# TOP_pcb_redonda_intento_taladros.net
KiCad netlist of a schematic drawn in EAGLE
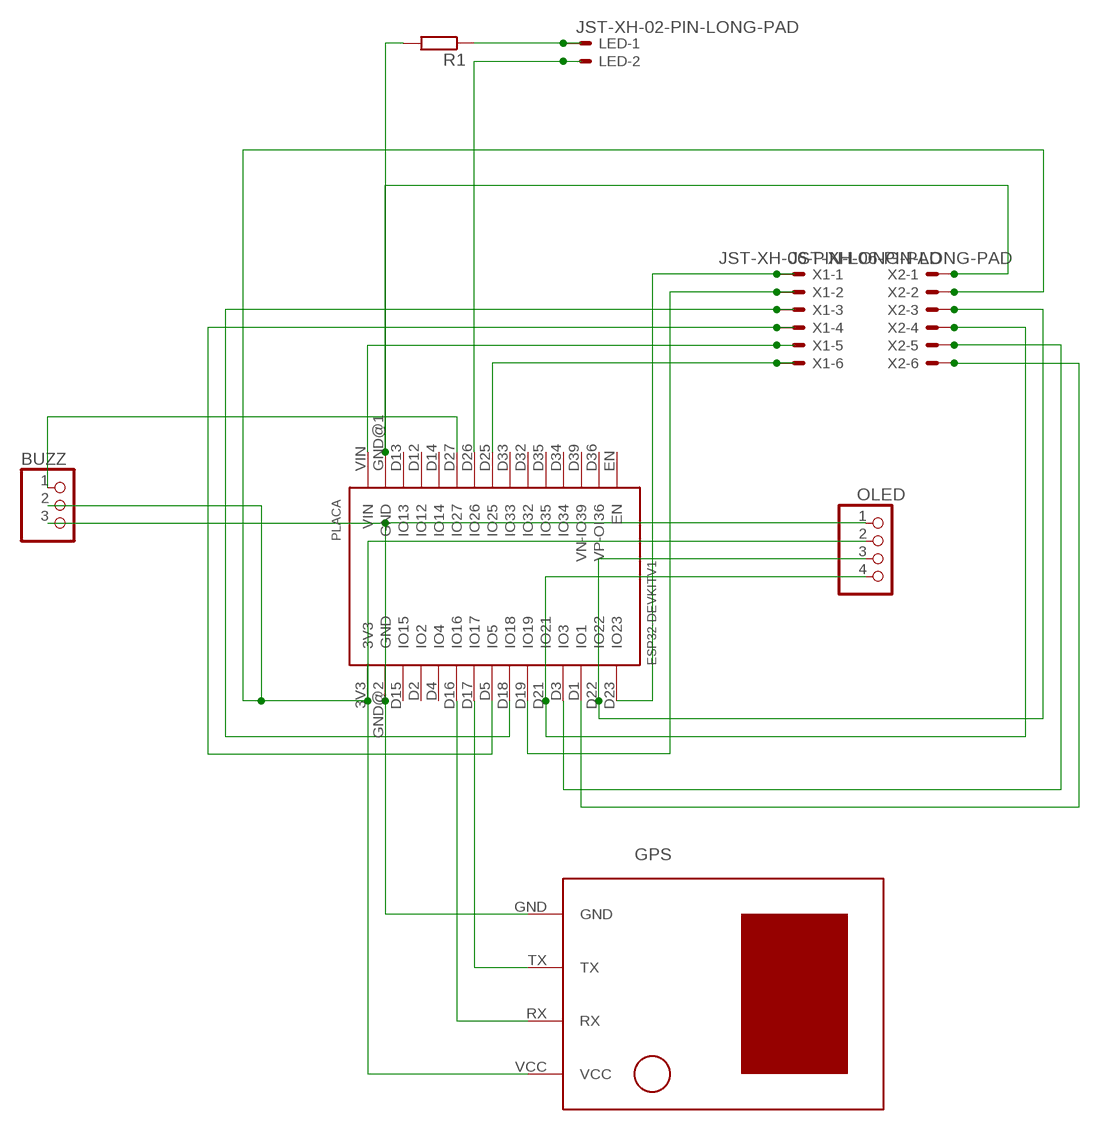
[diagram p0: schematic, sheet 1]

(export (version "E")
  (design (tool "Eeschema 10.0.6"))
  (components
    (comp (ref "BUZZ")
      (value "PINHD-1X3")
      (footprint "eagle-import:1X03")
      (libsource (lib "eagle-import") (part "PINHD-1X3"))
    )
    (comp (ref "GPS")
      (value "U-BLOX-NEO6V2")
      (footprint "eagle-import:U-BLOX-NEO6V2")
      (libsource (lib "eagle-import") (part "U-BLOX-NEO6V2"))
    )
    (comp (ref "LED")
      (value "JST-XH-02-PIN-LONG-PAD")
      (footprint "eagle-import:JST-XH-02-PACKAGE-LONG-PAD")
      (libsource (lib "eagle-import") (part "JST-XH-02-PIN-LONG-PAD"))
    )
    (comp (ref "OLED")
      (value "PINHD-1X4")
      (footprint "eagle-import:1X04")
      (libsource (lib "eagle-import") (part "PINHD-1X4"))
    )
    (comp (ref "PLACA")
      (value "ESP32DEVKITV1")
      (footprint "eagle-import:ESP32-DEVKITV1")
      (libsource (lib "eagle-import") (part "ESP32DEVKITV1"))
    )
    (comp (ref "R1")
      (value "R-EU_0207/10")
      (footprint "eagle-import:0207_10")
      (libsource (lib "eagle-import") (part "R-EU_0207/10"))
    )
    (comp (ref "X1")
      (value "JST-XH-06-PIN-LONG-PAD")
      (footprint "eagle-import:JST-XH-06-PACKAGE-LONG-PAD")
      (libsource (lib "eagle-import") (part "JST-XH-06-PIN-LONG-PAD"))
    )
    (comp (ref "X2")
      (value "JST-XH-06-PIN-LONG-PAD")
      (footprint "eagle-import:JST-XH-06-PACKAGE-LONG-PAD")
      (libsource (lib "eagle-import") (part "JST-XH-06-PIN-LONG-PAD"))
    )
  )
  (nets
    (net (code "1") (name "/GPS") (class "Default")
      (node (ref "BUZZ") (pin "3") (pinfunction "3_3") (pintype "passive"))
      (node (ref "GPS") (pin "GND") (pinfunction "GND_GND") (pintype "bidirectional"))
      (node (ref "OLED") (pin "1") (pinfunction "1_1") (pintype "passive"))
      (node (ref "PLACA") (pin "GND@2") (pinfunction "GND_GND@2") (pintype "bidirectional"))
    )
    (net (code "2") (name "Net-(LEDA-S)") (class "Default")
      (node (ref "LED") (pin "1") (pinfunction "S_1") (pintype "passive"))
      (node (ref "R1") (pin "1") (pinfunction "1_1") (pintype "passive"))
    )
    (net (code "3") (name "Net-(LEDB-S)") (class "Default")
      (node (ref "LED") (pin "2") (pinfunction "S_2") (pintype "passive"))
      (node (ref "PLACA") (pin "D26") (pinfunction "IO26_D26") (pintype "bidirectional"))
    )
    (net (code "4") (name "Net-(PLACA-IO1)") (class "Default")
      (node (ref "PLACA") (pin "D1") (pinfunction "IO1_D1") (pintype "bidirectional"))
      (node (ref "X2") (pin "6") (pinfunction "S_6") (pintype "passive"))
    )
    (net (code "5") (name "Net-(PLACA-IO3)") (class "Default")
      (node (ref "PLACA") (pin "D3") (pinfunction "IO3_D3") (pintype "bidirectional"))
      (node (ref "X2") (pin "5") (pinfunction "S_5") (pintype "passive"))
    )
    (net (code "6") (name "Net-(PLACA-IO5)") (class "Default")
      (node (ref "PLACA") (pin "D5") (pinfunction "IO5_D5") (pintype "bidirectional"))
      (node (ref "X1") (pin "4") (pinfunction "S_4") (pintype "passive"))
    )
    (net (code "7") (name "Net-(PLACA-IO16)") (class "Default")
      (node (ref "GPS") (pin "RX") (pinfunction "RX_RX") (pintype "bidirectional"))
      (node (ref "PLACA") (pin "D16") (pinfunction "IO16_D16") (pintype "bidirectional"))
    )
    (net (code "8") (name "Net-(PLACA-IO17)") (class "Default")
      (node (ref "GPS") (pin "TX") (pinfunction "TX_TX") (pintype "bidirectional"))
      (node (ref "PLACA") (pin "D17") (pinfunction "IO17_D17") (pintype "bidirectional"))
    )
    (net (code "9") (name "Net-(PLACA-IO18)") (class "Default")
      (node (ref "PLACA") (pin "D18") (pinfunction "IO18_D18") (pintype "bidirectional"))
      (node (ref "X1") (pin "3") (pinfunction "S_3") (pintype "passive"))
    )
    (net (code "10") (name "Net-(PLACA-IO19)") (class "Default")
      (node (ref "PLACA") (pin "D19") (pinfunction "IO19_D19") (pintype "bidirectional"))
      (node (ref "X1") (pin "2") (pinfunction "S_2") (pintype "passive"))
    )
    (net (code "11") (name "Net-(PLACA-IO21)") (class "Default")
      (node (ref "OLED") (pin "4") (pinfunction "4_4") (pintype "passive"))
      (node (ref "PLACA") (pin "D21") (pinfunction "IO21_D21") (pintype "bidirectional"))
      (node (ref "X2") (pin "4") (pinfunction "S_4") (pintype "passive"))
    )
    (net (code "12") (name "Net-(PLACA-IO22)") (class "Default")
      (node (ref "OLED") (pin "3") (pinfunction "3_3") (pintype "passive"))
      (node (ref "PLACA") (pin "D22") (pinfunction "IO22_D22") (pintype "bidirectional"))
      (node (ref "X2") (pin "3") (pinfunction "S_3") (pintype "passive"))
    )
    (net (code "13") (name "Net-(PLACA-IO23)") (class "Default")
      (node (ref "PLACA") (pin "D23") (pinfunction "IO23_D23") (pintype "bidirectional"))
      (node (ref "X1") (pin "1") (pinfunction "S_1") (pintype "passive"))
    )
    (net (code "14") (name "Net-(PLACA-IO25)") (class "Default")
      (node (ref "PLACA") (pin "D25") (pinfunction "IO25_D25") (pintype "bidirectional"))
      (node (ref "X1") (pin "6") (pinfunction "S_6") (pintype "passive"))
    )
    (net (code "15") (name "Net-(PLACA-IO27)") (class "Default")
      (node (ref "BUZZ") (pin "1") (pinfunction "1_1") (pintype "passive"))
      (node (ref "PLACA") (pin "D27") (pinfunction "IO27_D27") (pintype "bidirectional"))
    )
    (net (code "16") (name "Net-(X1E-S)") (class "Default")
      (node (ref "PLACA") (pin "VIN") (pinfunction "VIN_VIN") (pintype "bidirectional"))
      (node (ref "X1") (pin "5") (pinfunction "S_5") (pintype "passive"))
    )
    (net (code "17") (name "Net-(X2A-S)") (class "Default")
      (node (ref "PLACA") (pin "GND@1") (pinfunction "GND_GND@1") (pintype "bidirectional"))
      (node (ref "R1") (pin "2") (pinfunction "2_2") (pintype "passive"))
      (node (ref "X2") (pin "1") (pinfunction "S_1") (pintype "passive"))
    )
    (net (code "18") (name "Net-(X2B-S)") (class "Default")
      (node (ref "BUZZ") (pin "2") (pinfunction "2_2") (pintype "passive"))
      (node (ref "GPS") (pin "VCC") (pinfunction "VCC_VCC") (pintype "bidirectional"))
      (node (ref "OLED") (pin "2") (pinfunction "2_2") (pintype "passive"))
      (node (ref "PLACA") (pin "3V3") (pinfunction "3V3_3V3") (pintype "bidirectional"))
      (node (ref "X2") (pin "2") (pinfunction "S_2") (pintype "passive"))
    )
    (net (code "19") (name "unconnected-(PLACA-IO2-PadD2)") (class "Default")
      (node (ref "PLACA") (pin "D2") (pinfunction "IO2_D2") (pintype "bidirectional"))
    )
    (net (code "20") (name "unconnected-(PLACA-IO4-PadD4)") (class "Default")
      (node (ref "PLACA") (pin "D4") (pinfunction "IO4_D4") (pintype "bidirectional"))
    )
    (net (code "21") (name "unconnected-(PLACA-IO12-PadD12)") (class "Default")
      (node (ref "PLACA") (pin "D12") (pinfunction "IO12_D12") (pintype "bidirectional"))
    )
    (net (code "22") (name "unconnected-(PLACA-IO13-PadD13)") (class "Default")
      (node (ref "PLACA") (pin "D13") (pinfunction "IO13_D13") (pintype "bidirectional"))
    )
    (net (code "23") (name "unconnected-(PLACA-IO14-PadD14)") (class "Default")
      (node (ref "PLACA") (pin "D14") (pinfunction "IO14_D14") (pintype "bidirectional"))
    )
    (net (code "24") (name "unconnected-(PLACA-IO15-PadD15)") (class "Default")
      (node (ref "PLACA") (pin "D15") (pinfunction "IO15_D15") (pintype "bidirectional"))
    )
    (net (code "25") (name "unconnected-(PLACA-IO32-PadD32)") (class "Default")
      (node (ref "PLACA") (pin "D32") (pinfunction "IO32_D32") (pintype "bidirectional"))
    )
    (net (code "26") (name "unconnected-(PLACA-IO33-PadD33)") (class "Default")
      (node (ref "PLACA") (pin "D33") (pinfunction "IO33_D33") (pintype "bidirectional"))
    )
    (net (code "27") (name "unconnected-(PLACA-IO34-PadD34)") (class "Default")
      (node (ref "PLACA") (pin "D34") (pinfunction "IO34_D34") (pintype "bidirectional"))
    )
    (net (code "28") (name "unconnected-(PLACA-IO35-PadD35)") (class "Default")
      (node (ref "PLACA") (pin "D35") (pinfunction "IO35_D35") (pintype "bidirectional"))
    )
    (net (code "29") (name "unconnected-(PLACA-PadEN)") (class "Default")
      (node (ref "PLACA") (pin "EN") (pinfunction "EN_EN") (pintype "bidirectional"))
    )
    (net (code "30") (name "unconnected-(PLACA-VN-IO39-PadD39)") (class "Default")
      (node (ref "PLACA") (pin "D39") (pinfunction "VN-IO39_D39") (pintype "bidirectional"))
    )
    (net (code "31") (name "unconnected-(PLACA-VP-OI36-PadD36)") (class "Default")
      (node (ref "PLACA") (pin "D36") (pinfunction "VP-OI36_D36") (pintype "bidirectional"))
    )
  )
)
